# doanthue_13_4_2020.net
KiCad netlist of a schematic drawn in Altium Designer
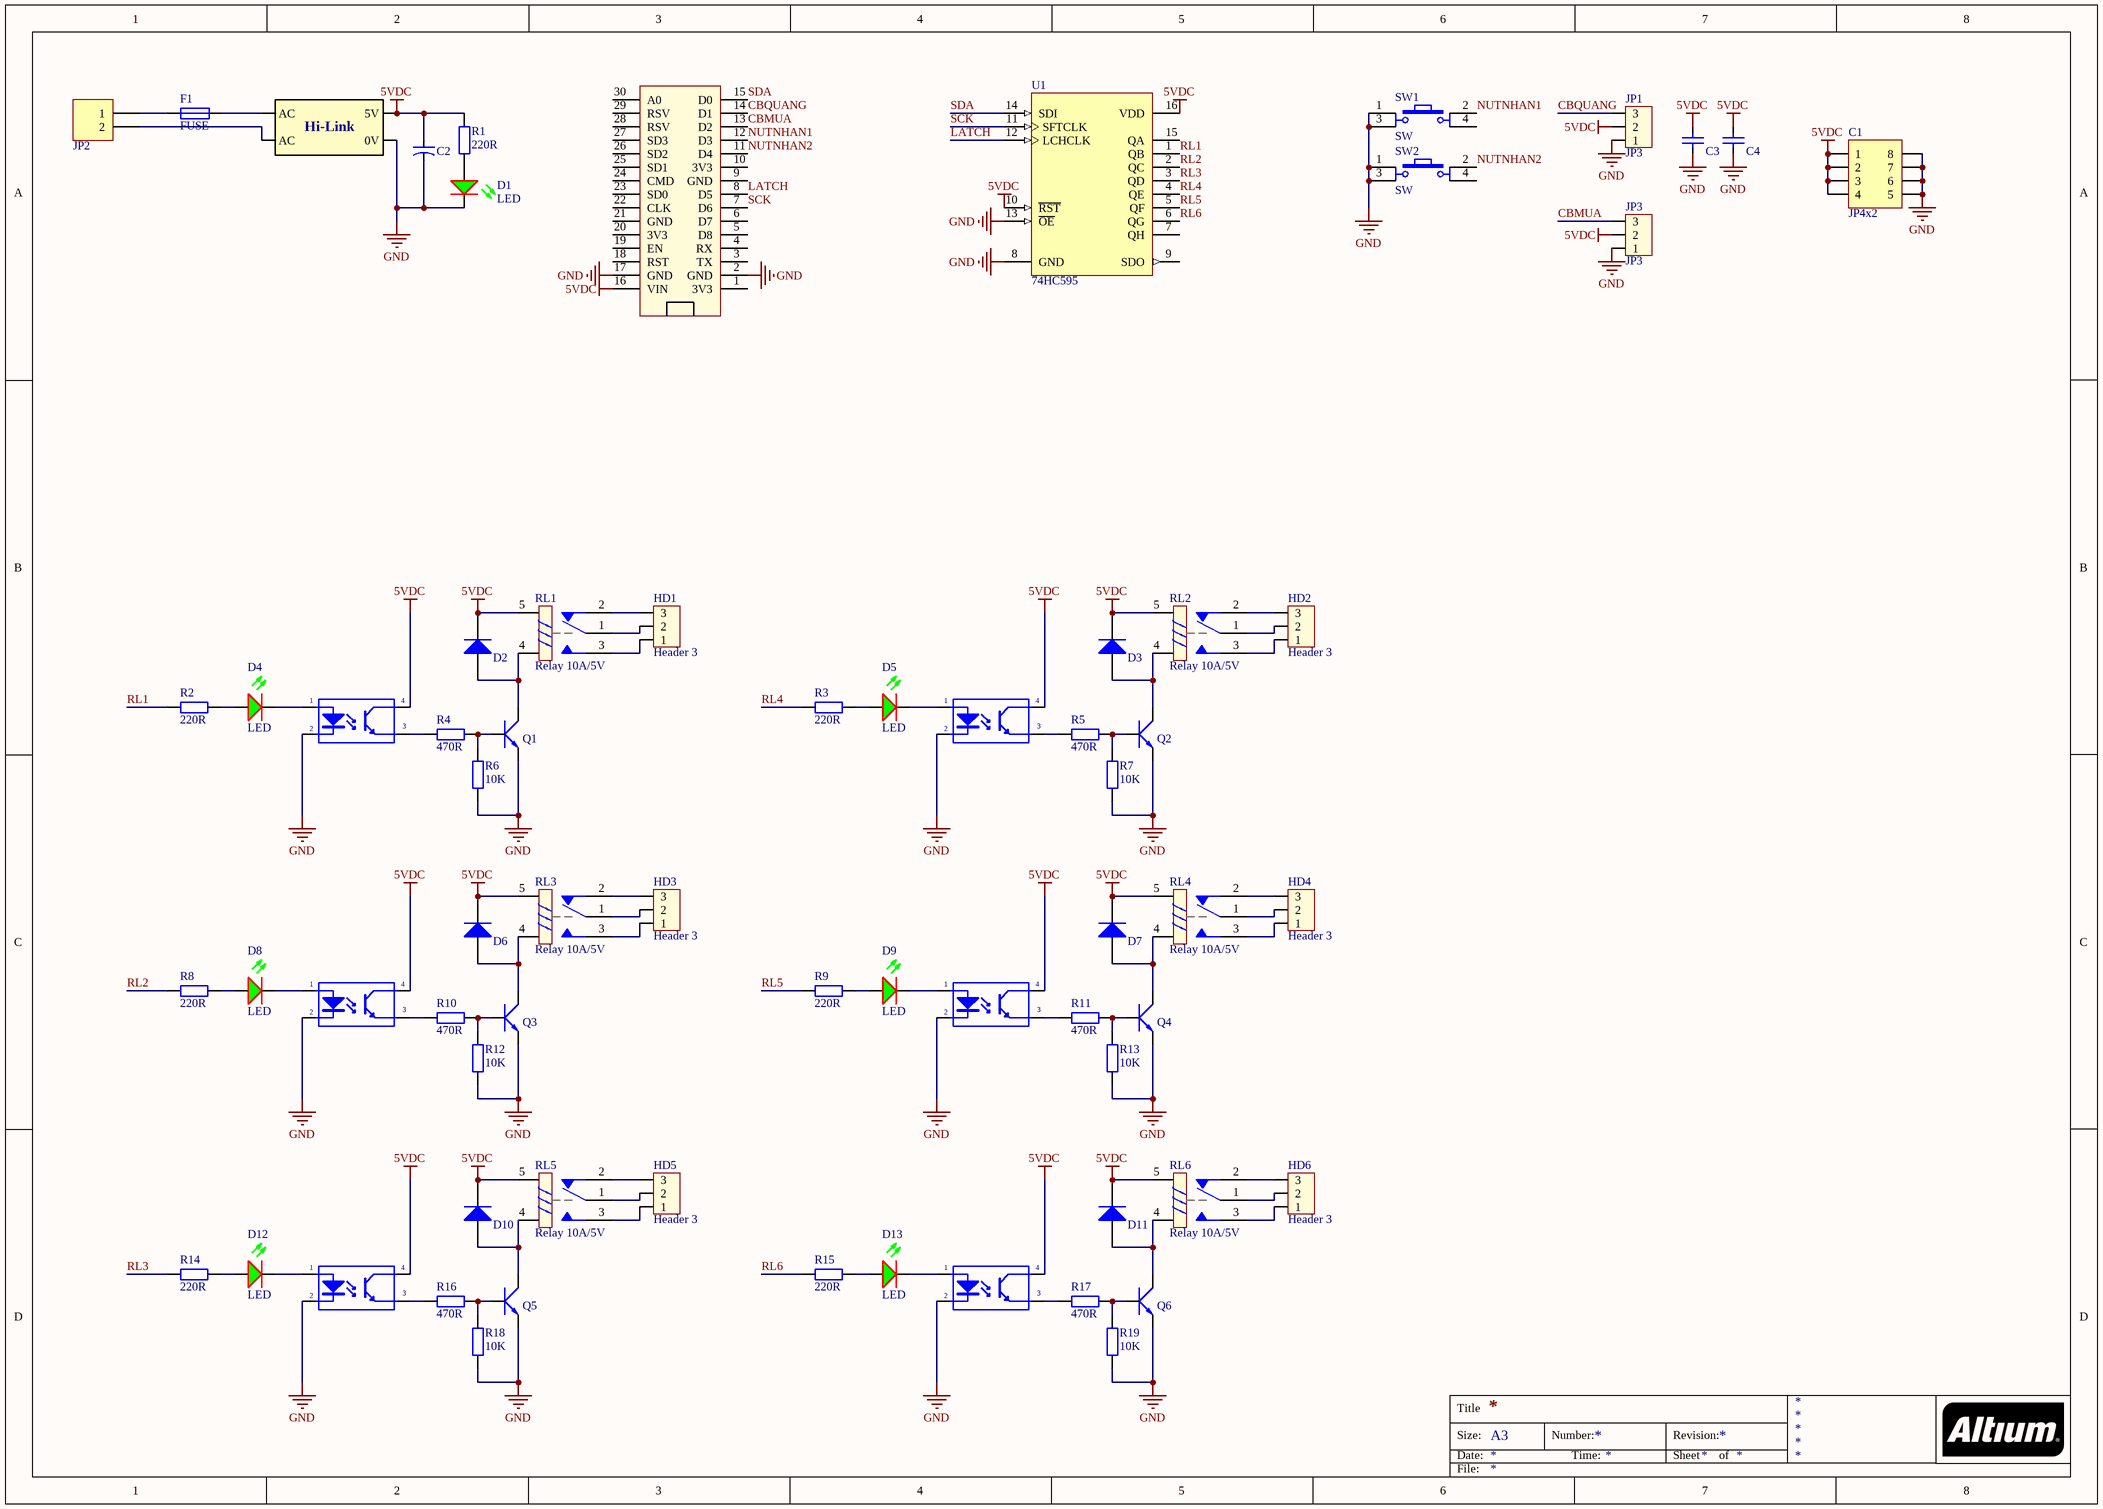
[diagram p0: doanthue_13_4_2020.SchDoc]

(export (version "E")
  (design (tool "Eeschema 10.0.6"))
  (components
    (comp (ref "*1")
      (value "Hi-Link")
      (footprint "Hi-Link")
      (libsource (lib "Lib_NTD_HaUI") (part "Hi-Link"))
    )
    (comp (ref "*2")
      (value "Module ESP8266 CP2102")
      (footprint "Module ESP8266 CP2102")
      (libsource (lib "Lib_NTD_HaUI") (part "Module ESP8266 CP2102"))
    )
    (comp (ref "C1")
      (value "JP4x2")
      (footprint "JP4-D2T")
      (description "WR-PHD 2.54 mm Dual Socket Header")
      (fields
        (field (name "MANUFACTURER") "Würth Elektronik eiSos GmbH")
        (field (name "PARTNO") "61300821821")
        (field (name "CREATED BY") "Karrer Zheng")
      )
      (libsource (lib "LIBRARY") (part "JP4x2"))
    )
    (comp (ref "C2")
      (value "10uF")
      (footprint "CA-ALU-2.54")
      (description "Capacitor (Semiconductor SIM Model)")
      (fields (field (name "PUBLISHER") "Altium Limited"))
      (libsource (lib "LIBRARY") (part "CN-ALU-DIP"))
    )
    (comp (ref "C3")
      (value "0805 104")
      (footprint "CAP-0805-SC")
      (libsource (lib "AltiumLibraryTieuBao") (part "CAP-SMDCHIP"))
    )
    (comp (ref "C4")
      (value "0805 104")
      (footprint "CAP-0805-SC")
      (libsource (lib "AltiumLibraryTieuBao") (part "CAP-SMDCHIP"))
    )
    (comp (ref "D1")
      (value "LED")
      (footprint "LED_SMD_0805")
      (libsource (lib "AltiumLibraryTieuBao") (part "LED"))
    )
    (comp (ref "D2") (value "DIODE") (footprint "DO 214AC") (libsource (lib "Lib_NTD_HaUI") (part "DIODE")))
    (comp (ref "D3") (value "DIODE") (footprint "DO 214AC") (libsource (lib "Lib_NTD_HaUI") (part "DIODE")))
    (comp (ref "D4")
      (value "LED")
      (footprint "LED_SMD_0805")
      (libsource (lib "AltiumLibraryTieuBao") (part "LED"))
    )
    (comp (ref "D5")
      (value "LED")
      (footprint "LED_SMD_0805")
      (libsource (lib "AltiumLibraryTieuBao") (part "LED"))
    )
    (comp (ref "D6") (value "DIODE") (footprint "DO 214AC") (libsource (lib "Lib_NTD_HaUI") (part "DIODE")))
    (comp (ref "D7") (value "DIODE") (footprint "DO 214AC") (libsource (lib "Lib_NTD_HaUI") (part "DIODE")))
    (comp (ref "D8")
      (value "LED")
      (footprint "LED_SMD_0805")
      (libsource (lib "AltiumLibraryTieuBao") (part "LED"))
    )
    (comp (ref "D9")
      (value "LED")
      (footprint "LED_SMD_0805")
      (libsource (lib "AltiumLibraryTieuBao") (part "LED"))
    )
    (comp (ref "D10") (value "DIODE") (footprint "DO 214AC") (libsource (lib "Lib_NTD_HaUI") (part "DIODE")))
    (comp (ref "D11") (value "DIODE") (footprint "DO 214AC") (libsource (lib "Lib_NTD_HaUI") (part "DIODE")))
    (comp (ref "D12")
      (value "LED")
      (footprint "LED_SMD_0805")
      (libsource (lib "AltiumLibraryTieuBao") (part "LED"))
    )
    (comp (ref "D13")
      (value "LED")
      (footprint "LED_SMD_0805")
      (libsource (lib "AltiumLibraryTieuBao") (part "LED"))
    )
    (comp (ref "F1")
      (value "FUSE")
      (footprint "FUSE-SC")
      (libsource (lib "AltiumLibraryTieuBao") (part "FUSE"))
    )
    (comp (ref "HD1")
      (value "Header 3")
      (footprint "HED3")
      (description "Header 3 (Green)")
      (libsource (lib "syhaunguyen") (part "Hed3"))
    )
    (comp (ref "HD2")
      (value "Header 3")
      (footprint "HED3")
      (description "Header 3 (Green)")
      (libsource (lib "syhaunguyen") (part "Hed3"))
    )
    (comp (ref "HD3")
      (value "Header 3")
      (footprint "HED3")
      (description "Header 3 (Green)")
      (libsource (lib "syhaunguyen") (part "Hed3"))
    )
    (comp (ref "HD4")
      (value "Header 3")
      (footprint "HED3")
      (description "Header 3 (Green)")
      (libsource (lib "syhaunguyen") (part "Hed3"))
    )
    (comp (ref "HD5")
      (value "Header 3")
      (footprint "HED3")
      (description "Header 3 (Green)")
      (libsource (lib "syhaunguyen") (part "Hed3"))
    )
    (comp (ref "HD6")
      (value "Header 3")
      (footprint "HED3")
      (description "Header 3 (Green)")
      (libsource (lib "syhaunguyen") (part "Hed3"))
    )
    (comp (ref "JP1")
      (value "JP3")
      (footprint "CON3")
      (description "Connector 3")
      (libsource (lib "syhaunguyen") (part "Con3"))
    )
    (comp (ref "JP2")
      (value "Header 2_1")
      (footprint "HED2")
      (description "Header, 2-Pin")
      (fields (field (name "MANUFACTURER") "Generic Components"))
      (libsource (lib "syhaunguyen") (part "Header 2_1"))
    )
    (comp (ref "JP3")
      (value "JP3")
      (footprint "CON3")
      (description "Connector 3")
      (libsource (lib "syhaunguyen") (part "Con3"))
    )
    (comp (ref "Q1") (value "C1815") (footprint "SOT23") (libsource (lib "Lib_NTD_HaUI") (part "C1815")))
    (comp (ref "Q2") (value "C1815") (footprint "SOT23") (libsource (lib "Lib_NTD_HaUI") (part "C1815")))
    (comp (ref "Q3") (value "C1815") (footprint "SOT23") (libsource (lib "Lib_NTD_HaUI") (part "C1815")))
    (comp (ref "Q4") (value "C1815") (footprint "SOT23") (libsource (lib "Lib_NTD_HaUI") (part "C1815")))
    (comp (ref "Q5") (value "C1815") (footprint "SOT23") (libsource (lib "Lib_NTD_HaUI") (part "C1815")))
    (comp (ref "Q6") (value "C1815") (footprint "SOT23") (libsource (lib "Lib_NTD_HaUI") (part "C1815")))
    (comp (ref "R1")
      (value "220R")
      (footprint "SM-RES-0805")
      (description "Resistor 1/4W")
      (libsource (lib "syhaunguyen") (part "R1/4W"))
    )
    (comp (ref "R2")
      (value "220R")
      (footprint "SM-RES-0805")
      (description "Resistor 1/4W")
      (libsource (lib "syhaunguyen") (part "R1/4W"))
    )
    (comp (ref "R3")
      (value "220R")
      (footprint "SM-RES-0805")
      (description "Resistor 1/4W")
      (libsource (lib "syhaunguyen") (part "R1/4W"))
    )
    (comp (ref "R4")
      (value "470R")
      (footprint "SM-RES-0805")
      (description "Resistor 1/4W")
      (libsource (lib "syhaunguyen") (part "R1/4W"))
    )
    (comp (ref "R5")
      (value "470R")
      (footprint "SM-RES-0805")
      (description "Resistor 1/4W")
      (libsource (lib "syhaunguyen") (part "R1/4W"))
    )
    (comp (ref "R6")
      (value "10K")
      (footprint "SM-RES-0805")
      (description "Resistor 1/4W")
      (libsource (lib "syhaunguyen") (part "R1/4W"))
    )
    (comp (ref "R7")
      (value "10K")
      (footprint "SM-RES-0805")
      (description "Resistor 1/4W")
      (libsource (lib "syhaunguyen") (part "R1/4W"))
    )
    (comp (ref "R8")
      (value "220R")
      (footprint "SM-RES-0805")
      (description "Resistor 1/4W")
      (libsource (lib "syhaunguyen") (part "R1/4W"))
    )
    (comp (ref "R9")
      (value "220R")
      (footprint "SM-RES-0805")
      (description "Resistor 1/4W")
      (libsource (lib "syhaunguyen") (part "R1/4W"))
    )
    (comp (ref "R10")
      (value "470R")
      (footprint "SM-RES-0805")
      (description "Resistor 1/4W")
      (libsource (lib "syhaunguyen") (part "R1/4W"))
    )
    (comp (ref "R11")
      (value "470R")
      (footprint "SM-RES-0805")
      (description "Resistor 1/4W")
      (libsource (lib "syhaunguyen") (part "R1/4W"))
    )
    (comp (ref "R12")
      (value "10K")
      (footprint "SM-RES-0805")
      (description "Resistor 1/4W")
      (libsource (lib "syhaunguyen") (part "R1/4W"))
    )
    (comp (ref "R13")
      (value "10K")
      (footprint "SM-RES-0805")
      (description "Resistor 1/4W")
      (libsource (lib "syhaunguyen") (part "R1/4W"))
    )
    (comp (ref "R14")
      (value "220R")
      (footprint "SM-RES-0805")
      (description "Resistor 1/4W")
      (libsource (lib "syhaunguyen") (part "R1/4W"))
    )
    (comp (ref "R15")
      (value "220R")
      (footprint "SM-RES-0805")
      (description "Resistor 1/4W")
      (libsource (lib "syhaunguyen") (part "R1/4W"))
    )
    (comp (ref "R16")
      (value "470R")
      (footprint "SM-RES-0805")
      (description "Resistor 1/4W")
      (libsource (lib "syhaunguyen") (part "R1/4W"))
    )
    (comp (ref "R17")
      (value "470R")
      (footprint "SM-RES-0805")
      (description "Resistor 1/4W")
      (libsource (lib "syhaunguyen") (part "R1/4W"))
    )
    (comp (ref "R18")
      (value "10K")
      (footprint "SM-RES-0805")
      (description "Resistor 1/4W")
      (libsource (lib "syhaunguyen") (part "R1/4W"))
    )
    (comp (ref "R19")
      (value "10K")
      (footprint "SM-RES-0805")
      (description "Resistor 1/4W")
      (libsource (lib "syhaunguyen") (part "R1/4W"))
    )
    (comp (ref "RL1")
      (value "Relay 10A/5V")
      (footprint "RL_SPDT_10A")
      (description "Relay SPDT,10A - 12VDC 5 Pin")
      (libsource (lib "syhaunguyen") (part "Relay 1"))
    )
    (comp (ref "RL2")
      (value "Relay 10A/5V")
      (footprint "RL_SPDT_10A")
      (description "Relay SPDT,10A - 12VDC 5 Pin")
      (libsource (lib "syhaunguyen") (part "Relay 1"))
    )
    (comp (ref "RL3")
      (value "Relay 10A/5V")
      (footprint "RL_SPDT_10A")
      (description "Relay SPDT,10A - 12VDC 5 Pin")
      (libsource (lib "syhaunguyen") (part "Relay 1"))
    )
    (comp (ref "RL4")
      (value "Relay 10A/5V")
      (footprint "RL_SPDT_10A")
      (description "Relay SPDT,10A - 12VDC 5 Pin")
      (libsource (lib "syhaunguyen") (part "Relay 1"))
    )
    (comp (ref "RL5")
      (value "Relay 10A/5V")
      (footprint "RL_SPDT_10A")
      (description "Relay SPDT,10A - 12VDC 5 Pin")
      (libsource (lib "syhaunguyen") (part "Relay 1"))
    )
    (comp (ref "RL6")
      (value "Relay 10A/5V")
      (footprint "RL_SPDT_10A")
      (description "Relay SPDT,10A - 12VDC 5 Pin")
      (libsource (lib "syhaunguyen") (part "Relay 1"))
    )
    (comp (ref "SW1")
      (value "SW")
      (footprint "SW4B")
      (description "Switch button 4 pin")
      (libsource (lib "syhaunguyen") (part "SW4"))
    )
    (comp (ref "SW2")
      (value "SW")
      (footprint "SW4B")
      (description "Switch button 4 pin")
      (libsource (lib "syhaunguyen") (part "SW4"))
    )
    (comp (ref "U1")
      (value "74HC595")
      (footprint "SO-16-M")
      (libsource (lib "AltiumLibraryTieuBao") (part "74HC595"))
    )
    (comp (ref "U2") (value "PC817") (footprint "PC817") (libsource (lib "Lib_NTD_HaUI") (part "PC817")))
    (comp (ref "U3") (value "PC817") (footprint "PC817") (libsource (lib "Lib_NTD_HaUI") (part "PC817")))
    (comp (ref "U4") (value "PC817") (footprint "PC817") (libsource (lib "Lib_NTD_HaUI") (part "PC817")))
    (comp (ref "U5") (value "PC817") (footprint "PC817") (libsource (lib "Lib_NTD_HaUI") (part "PC817")))
    (comp (ref "U6") (value "PC817") (footprint "PC817") (libsource (lib "Lib_NTD_HaUI") (part "PC817")))
    (comp (ref "U7") (value "PC817") (footprint "PC817") (libsource (lib "Lib_NTD_HaUI") (part "PC817")))
  )
  (nets
    (net (code "1") (name "/CBMUA") (class "Default")
      (node (ref "*2") (pin "13") (pinfunction "D2_13") (pintype "passive"))
      (node (ref "JP3") (pin "3") (pinfunction "3_3") (pintype "passive"))
    )
    (net (code "2") (name "/CBQUANG") (class "Default")
      (node (ref "*2") (pin "14") (pinfunction "D1_14") (pintype "passive"))
      (node (ref "JP1") (pin "3") (pinfunction "3_3") (pintype "passive"))
    )
    (net (code "3") (name "/LATCH") (class "Default")
      (node (ref "*2") (pin "8") (pinfunction "D5_8") (pintype "passive"))
      (node (ref "U1") (pin "12") (pinfunction "LCHCLK_12") (pintype "input"))
    )
    (net (code "4") (name "/NUTNHAN1") (class "Default")
      (node (ref "*2") (pin "12") (pinfunction "D3_12") (pintype "passive"))
      (node (ref "SW1") (pin "2") (pintype "passive"))
    )
    (net (code "5") (name "/NUTNHAN2") (class "Default")
      (node (ref "*2") (pin "11") (pinfunction "D4_11") (pintype "passive"))
      (node (ref "SW2") (pin "2") (pintype "passive"))
    )
    (net (code "6") (name "/RL1") (class "Default")
      (node (ref "R2") (pin "1") (pinfunction "1_1") (pintype "passive"))
      (node (ref "U1") (pin "1") (pinfunction "QB_1") (pintype "tri_state"))
    )
    (net (code "7") (name "/RL2") (class "Default")
      (node (ref "R8") (pin "1") (pinfunction "1_1") (pintype "passive"))
      (node (ref "U1") (pin "2") (pinfunction "QC_2") (pintype "tri_state"))
    )
    (net (code "8") (name "/RL3") (class "Default")
      (node (ref "R14") (pin "1") (pinfunction "1_1") (pintype "passive"))
      (node (ref "U1") (pin "3") (pinfunction "QD_3") (pintype "tri_state"))
    )
    (net (code "9") (name "/RL4") (class "Default")
      (node (ref "R3") (pin "1") (pinfunction "1_1") (pintype "passive"))
      (node (ref "U1") (pin "4") (pinfunction "QE_4") (pintype "tri_state"))
    )
    (net (code "10") (name "/RL5") (class "Default")
      (node (ref "R9") (pin "1") (pinfunction "1_1") (pintype "passive"))
      (node (ref "U1") (pin "5") (pinfunction "QF_5") (pintype "tri_state"))
    )
    (net (code "11") (name "/RL6") (class "Default")
      (node (ref "R15") (pin "1") (pinfunction "1_1") (pintype "passive"))
      (node (ref "U1") (pin "6") (pinfunction "QG_6") (pintype "tri_state"))
    )
    (net (code "12") (name "/SCK") (class "Default")
      (node (ref "*2") (pin "7") (pinfunction "D6_7") (pintype "passive"))
      (node (ref "U1") (pin "11") (pinfunction "SFTCLK_11") (pintype "input"))
    )
    (net (code "13") (name "/SDA") (class "Default")
      (node (ref "*2") (pin "15") (pinfunction "D0_15") (pintype "passive"))
      (node (ref "U1") (pin "14") (pinfunction "SDI_14") (pintype "input"))
    )
    (net (code "14") (name "5VDC") (class "Default")
      (node (ref "*1") (pin "4") (pinfunction "5V_4") (pintype "passive"))
      (node (ref "*2") (pin "16") (pinfunction "VIN_16") (pintype "passive"))
      (node (ref "C1") (pin "1") (pinfunction "1_1") (pintype "passive"))
      (node (ref "C1") (pin "2") (pinfunction "2_2") (pintype "passive"))
      (node (ref "C1") (pin "3") (pinfunction "3_3") (pintype "passive"))
      (node (ref "C1") (pin "4") (pinfunction "4_4") (pintype "passive"))
      (node (ref "C2") (pin "1") (pinfunction "1_1") (pintype "passive"))
      (node (ref "C3") (pin "1") (pinfunction "1_1") (pintype "passive"))
      (node (ref "C4") (pin "1") (pinfunction "1_1") (pintype "passive"))
      (node (ref "D10") (pin "2") (pinfunction "K_2") (pintype "passive"))
      (node (ref "D11") (pin "2") (pinfunction "K_2") (pintype "passive"))
      (node (ref "D2") (pin "2") (pinfunction "K_2") (pintype "passive"))
      (node (ref "D3") (pin "2") (pinfunction "K_2") (pintype "passive"))
      (node (ref "D6") (pin "2") (pinfunction "K_2") (pintype "passive"))
      (node (ref "D7") (pin "2") (pinfunction "K_2") (pintype "passive"))
      (node (ref "JP1") (pin "2") (pinfunction "2_2") (pintype "passive"))
      (node (ref "JP3") (pin "2") (pinfunction "2_2") (pintype "passive"))
      (node (ref "R1") (pin "2") (pinfunction "2_2") (pintype "passive"))
      (node (ref "RL1") (pin "5") (pinfunction "5_5") (pintype "passive"))
      (node (ref "RL2") (pin "5") (pinfunction "5_5") (pintype "passive"))
      (node (ref "RL3") (pin "5") (pinfunction "5_5") (pintype "passive"))
      (node (ref "RL4") (pin "5") (pinfunction "5_5") (pintype "passive"))
      (node (ref "RL5") (pin "5") (pinfunction "5_5") (pintype "passive"))
      (node (ref "RL6") (pin "5") (pinfunction "5_5") (pintype "passive"))
      (node (ref "U1") (pin "10") (pinfunction "~{RST}_10") (pintype "input"))
      (node (ref "U1") (pin "16") (pinfunction "VDD_16") (pintype "power_in"))
      (node (ref "U2") (pin "4") (pinfunction "C_4") (pintype "passive"))
      (node (ref "U3") (pin "4") (pinfunction "C_4") (pintype "passive"))
      (node (ref "U4") (pin "4") (pinfunction "C_4") (pintype "passive"))
      (node (ref "U5") (pin "4") (pinfunction "C_4") (pintype "passive"))
      (node (ref "U6") (pin "4") (pinfunction "C_4") (pintype "passive"))
      (node (ref "U7") (pin "4") (pinfunction "C_4") (pintype "passive"))
    )
    (net (code "15") (name "GND") (class "Default")
      (node (ref "*1") (pin "3") (pinfunction "0V_3") (pintype "passive"))
      (node (ref "*2") (pin "17") (pinfunction "GND_17") (pintype "passive"))
      (node (ref "*2") (pin "2") (pinfunction "GND_2") (pintype "passive"))
      (node (ref "C1") (pin "5") (pinfunction "5_5") (pintype "passive"))
      (node (ref "C1") (pin "6") (pinfunction "6_6") (pintype "passive"))
      (node (ref "C1") (pin "7") (pinfunction "7_7") (pintype "passive"))
      (node (ref "C1") (pin "8") (pinfunction "8_8") (pintype "passive"))
      (node (ref "C2") (pin "2") (pinfunction "2_2") (pintype "passive"))
      (node (ref "C3") (pin "2") (pinfunction "2_2") (pintype "passive"))
      (node (ref "C4") (pin "2") (pinfunction "2_2") (pintype "passive"))
      (node (ref "D1") (pin "2") (pinfunction "K_2") (pintype "passive"))
      (node (ref "JP1") (pin "1") (pinfunction "1_1") (pintype "passive"))
      (node (ref "JP3") (pin "1") (pinfunction "1_1") (pintype "passive"))
      (node (ref "Q1") (pin "2") (pinfunction "E_2") (pintype "passive"))
      (node (ref "Q2") (pin "2") (pinfunction "E_2") (pintype "passive"))
      (node (ref "Q3") (pin "2") (pinfunction "E_2") (pintype "passive"))
      (node (ref "Q4") (pin "2") (pinfunction "E_2") (pintype "passive"))
      (node (ref "Q5") (pin "2") (pinfunction "E_2") (pintype "passive"))
      (node (ref "Q6") (pin "2") (pinfunction "E_2") (pintype "passive"))
      (node (ref "R12") (pin "1") (pinfunction "1_1") (pintype "passive"))
      (node (ref "R13") (pin "1") (pinfunction "1_1") (pintype "passive"))
      (node (ref "R18") (pin "1") (pinfunction "1_1") (pintype "passive"))
      (node (ref "R19") (pin "1") (pinfunction "1_1") (pintype "passive"))
      (node (ref "R6") (pin "1") (pinfunction "1_1") (pintype "passive"))
      (node (ref "R7") (pin "1") (pinfunction "1_1") (pintype "passive"))
      (node (ref "SW1") (pin "1") (pintype "passive"))
      (node (ref "SW1") (pin "3") (pintype "passive"))
      (node (ref "SW2") (pin "1") (pintype "passive"))
      (node (ref "SW2") (pin "3") (pintype "passive"))
      (node (ref "U1") (pin "13") (pinfunction "~{OE}_13") (pintype "input"))
      (node (ref "U1") (pin "8") (pinfunction "GND_8") (pintype "power_in"))
      (node (ref "U2") (pin "2") (pinfunction "K_2") (pintype "passive"))
      (node (ref "U3") (pin "2") (pinfunction "K_2") (pintype "passive"))
      (node (ref "U4") (pin "2") (pinfunction "K_2") (pintype "passive"))
      (node (ref "U5") (pin "2") (pinfunction "K_2") (pintype "passive"))
      (node (ref "U6") (pin "2") (pinfunction "K_2") (pintype "passive"))
      (node (ref "U7") (pin "2") (pinfunction "K_2") (pintype "passive"))
    )
    (net (code "16") (name "Net-(*1-AC-Pad2)") (class "Default")
      (node (ref "*1") (pin "2") (pinfunction "AC_2") (pintype "passive"))
      (node (ref "JP2") (pin "2") (pinfunction "2_2") (pintype "passive"))
    )
    (net (code "17") (name "Net-(D1-A)") (class "Default")
      (node (ref "D1") (pin "1") (pinfunction "A_1") (pintype "passive"))
      (node (ref "R1") (pin "1") (pinfunction "1_1") (pintype "passive"))
    )
    (net (code "18") (name "Net-(D2-A)") (class "Default")
      (node (ref "D2") (pin "1") (pinfunction "A_1") (pintype "passive"))
      (node (ref "Q1") (pin "3") (pinfunction "C_3") (pintype "passive"))
      (node (ref "RL1") (pin "4") (pinfunction "4_4") (pintype "passive"))
    )
    (net (code "19") (name "Net-(D3-A)") (class "Default")
      (node (ref "D3") (pin "1") (pinfunction "A_1") (pintype "passive"))
      (node (ref "Q2") (pin "3") (pinfunction "C_3") (pintype "passive"))
      (node (ref "RL2") (pin "4") (pinfunction "4_4") (pintype "passive"))
    )
    (net (code "20") (name "Net-(D4-A)") (class "Default")
      (node (ref "D4") (pin "1") (pinfunction "A_1") (pintype "passive"))
      (node (ref "R2") (pin "2") (pinfunction "2_2") (pintype "passive"))
    )
    (net (code "21") (name "Net-(D4-K)") (class "Default")
      (node (ref "D4") (pin "2") (pinfunction "K_2") (pintype "passive"))
      (node (ref "U2") (pin "1") (pinfunction "A_1") (pintype "passive"))
    )
    (net (code "22") (name "Net-(D5-A)") (class "Default")
      (node (ref "D5") (pin "1") (pinfunction "A_1") (pintype "passive"))
      (node (ref "R3") (pin "2") (pinfunction "2_2") (pintype "passive"))
    )
    (net (code "23") (name "Net-(D5-K)") (class "Default")
      (node (ref "D5") (pin "2") (pinfunction "K_2") (pintype "passive"))
      (node (ref "U3") (pin "1") (pinfunction "A_1") (pintype "passive"))
    )
    (net (code "24") (name "Net-(D6-A)") (class "Default")
      (node (ref "D6") (pin "1") (pinfunction "A_1") (pintype "passive"))
      (node (ref "Q3") (pin "3") (pinfunction "C_3") (pintype "passive"))
      (node (ref "RL3") (pin "4") (pinfunction "4_4") (pintype "passive"))
    )
    (net (code "25") (name "Net-(D7-A)") (class "Default")
      (node (ref "D7") (pin "1") (pinfunction "A_1") (pintype "passive"))
      (node (ref "Q4") (pin "3") (pinfunction "C_3") (pintype "passive"))
      (node (ref "RL4") (pin "4") (pinfunction "4_4") (pintype "passive"))
    )
    (net (code "26") (name "Net-(D8-A)") (class "Default")
      (node (ref "D8") (pin "1") (pinfunction "A_1") (pintype "passive"))
      (node (ref "R8") (pin "2") (pinfunction "2_2") (pintype "passive"))
    )
    (net (code "27") (name "Net-(D8-K)") (class "Default")
      (node (ref "D8") (pin "2") (pinfunction "K_2") (pintype "passive"))
      (node (ref "U4") (pin "1") (pinfunction "A_1") (pintype "passive"))
    )
    (net (code "28") (name "Net-(D9-A)") (class "Default")
      (node (ref "D9") (pin "1") (pinfunction "A_1") (pintype "passive"))
      (node (ref "R9") (pin "2") (pinfunction "2_2") (pintype "passive"))
    )
    (net (code "29") (name "Net-(D9-K)") (class "Default")
      (node (ref "D9") (pin "2") (pinfunction "K_2") (pintype "passive"))
      (node (ref "U5") (pin "1") (pinfunction "A_1") (pintype "passive"))
    )
    (net (code "30") (name "Net-(D10-A)") (class "Default")
      (node (ref "D10") (pin "1") (pinfunction "A_1") (pintype "passive"))
      (node (ref "Q5") (pin "3") (pinfunction "C_3") (pintype "passive"))
      (node (ref "RL5") (pin "4") (pinfunction "4_4") (pintype "passive"))
    )
    (net (code "31") (name "Net-(D11-A)") (class "Default")
      (node (ref "D11") (pin "1") (pinfunction "A_1") (pintype "passive"))
      (node (ref "Q6") (pin "3") (pinfunction "C_3") (pintype "passive"))
      (node (ref "RL6") (pin "4") (pinfunction "4_4") (pintype "passive"))
    )
    (net (code "32") (name "Net-(D12-A)") (class "Default")
      (node (ref "D12") (pin "1") (pinfunction "A_1") (pintype "passive"))
      (node (ref "R14") (pin "2") (pinfunction "2_2") (pintype "passive"))
    )
    (net (code "33") (name "Net-(D12-K)") (class "Default")
      (node (ref "D12") (pin "2") (pinfunction "K_2") (pintype "passive"))
      (node (ref "U6") (pin "1") (pinfunction "A_1") (pintype "passive"))
    )
    (net (code "34") (name "Net-(D13-A)") (class "Default")
      (node (ref "D13") (pin "1") (pinfunction "A_1") (pintype "passive"))
      (node (ref "R15") (pin "2") (pinfunction "2_2") (pintype "passive"))
    )
    (net (code "35") (name "Net-(D13-K)") (class "Default")
      (node (ref "D13") (pin "2") (pinfunction "K_2") (pintype "passive"))
      (node (ref "U7") (pin "1") (pinfunction "A_1") (pintype "passive"))
    )
    (net (code "36") (name "Net-(F1-100)") (class "Default")
      (node (ref "*1") (pin "1") (pinfunction "AC_1") (pintype "passive"))
      (node (ref "F1") (pin "2") (pinfunction "100_2") (pintype "passive"))
    )
    (net (code "37") (name "Net-(F1-Pad1)") (class "Default")
      (node (ref "F1") (pin "1") (pinfunction "1_1") (pintype "passive"))
      (node (ref "JP2") (pin "1") (pinfunction "1_1") (pintype "passive"))
    )
    (net (code "38") (name "Net-(HD1-Pad1)") (class "Default")
      (node (ref "HD1") (pin "1") (pinfunction "1_1") (pintype "passive"))
      (node (ref "RL1") (pin "3") (pinfunction "3_3") (pintype "passive"))
    )
    (net (code "39") (name "Net-(HD1-Pad2)") (class "Default")
      (node (ref "HD1") (pin "2") (pinfunction "2_2") (pintype "passive"))
      (node (ref "RL1") (pin "1") (pinfunction "1_1") (pintype "passive"))
    )
    (net (code "40") (name "Net-(HD1-Pad3)") (class "Default")
      (node (ref "HD1") (pin "3") (pinfunction "3_3") (pintype "passive"))
      (node (ref "RL1") (pin "2") (pinfunction "2_2") (pintype "passive"))
    )
    (net (code "41") (name "Net-(HD2-Pad1)") (class "Default")
      (node (ref "HD2") (pin "1") (pinfunction "1_1") (pintype "passive"))
      (node (ref "RL2") (pin "3") (pinfunction "3_3") (pintype "passive"))
    )
    (net (code "42") (name "Net-(HD2-Pad2)") (class "Default")
      (node (ref "HD2") (pin "2") (pinfunction "2_2") (pintype "passive"))
      (node (ref "RL2") (pin "1") (pinfunction "1_1") (pintype "passive"))
    )
    (net (code "43") (name "Net-(HD2-Pad3)") (class "Default")
      (node (ref "HD2") (pin "3") (pinfunction "3_3") (pintype "passive"))
      (node (ref "RL2") (pin "2") (pinfunction "2_2") (pintype "passive"))
    )
    (net (code "44") (name "Net-(HD3-Pad1)") (class "Default")
      (node (ref "HD3") (pin "1") (pinfunction "1_1") (pintype "passive"))
      (node (ref "RL3") (pin "3") (pinfunction "3_3") (pintype "passive"))
    )
    (net (code "45") (name "Net-(HD3-Pad2)") (class "Default")
      (node (ref "HD3") (pin "2") (pinfunction "2_2") (pintype "passive"))
      (node (ref "RL3") (pin "1") (pinfunction "1_1") (pintype "passive"))
    )
    (net (code "46") (name "Net-(HD3-Pad3)") (class "Default")
      (node (ref "HD3") (pin "3") (pinfunction "3_3") (pintype "passive"))
      (node (ref "RL3") (pin "2") (pinfunction "2_2") (pintype "passive"))
    )
    (net (code "47") (name "Net-(HD4-Pad1)") (class "Default")
      (node (ref "HD4") (pin "1") (pinfunction "1_1") (pintype "passive"))
      (node (ref "RL4") (pin "3") (pinfunction "3_3") (pintype "passive"))
    )
    (net (code "48") (name "Net-(HD4-Pad2)") (class "Default")
      (node (ref "HD4") (pin "2") (pinfunction "2_2") (pintype "passive"))
      (node (ref "RL4") (pin "1") (pinfunction "1_1") (pintype "passive"))
    )
    (net (code "49") (name "Net-(HD4-Pad3)") (class "Default")
      (node (ref "HD4") (pin "3") (pinfunction "3_3") (pintype "passive"))
      (node (ref "RL4") (pin "2") (pinfunction "2_2") (pintype "passive"))
    )
    (net (code "50") (name "Net-(HD5-Pad1)") (class "Default")
      (node (ref "HD5") (pin "1") (pinfunction "1_1") (pintype "passive"))
      (node (ref "RL5") (pin "3") (pinfunction "3_3") (pintype "passive"))
    )
    (net (code "51") (name "Net-(HD5-Pad2)") (class "Default")
      (node (ref "HD5") (pin "2") (pinfunction "2_2") (pintype "passive"))
      (node (ref "RL5") (pin "1") (pinfunction "1_1") (pintype "passive"))
    )
    (net (code "52") (name "Net-(HD5-Pad3)") (class "Default")
      (node (ref "HD5") (pin "3") (pinfunction "3_3") (pintype "passive"))
      (node (ref "RL5") (pin "2") (pinfunction "2_2") (pintype "passive"))
    )
    (net (code "53") (name "Net-(HD6-Pad1)") (class "Default")
      (node (ref "HD6") (pin "1") (pinfunction "1_1") (pintype "passive"))
      (node (ref "RL6") (pin "3") (pinfunction "3_3") (pintype "passive"))
    )
    (net (code "54") (name "Net-(HD6-Pad2)") (class "Default")
      (node (ref "HD6") (pin "2") (pinfunction "2_2") (pintype "passive"))
      (node (ref "RL6") (pin "1") (pinfunction "1_1") (pintype "passive"))
    )
    (net (code "55") (name "Net-(HD6-Pad3)") (class "Default")
      (node (ref "HD6") (pin "3") (pinfunction "3_3") (pintype "passive"))
      (node (ref "RL6") (pin "2") (pinfunction "2_2") (pintype "passive"))
    )
    (net (code "56") (name "Net-(Q1-B)") (class "Default")
      (node (ref "Q1") (pin "1") (pinfunction "B_1") (pintype "passive"))
      (node (ref "R4") (pin "2") (pinfunction "2_2") (pintype "passive"))
      (node (ref "R6") (pin "2") (pinfunction "2_2") (pintype "passive"))
    )
    (net (code "57") (name "Net-(Q2-B)") (class "Default")
      (node (ref "Q2") (pin "1") (pinfunction "B_1") (pintype "passive"))
      (node (ref "R5") (pin "2") (pinfunction "2_2") (pintype "passive"))
      (node (ref "R7") (pin "2") (pinfunction "2_2") (pintype "passive"))
    )
    (net (code "58") (name "Net-(Q3-B)") (class "Default")
      (node (ref "Q3") (pin "1") (pinfunction "B_1") (pintype "passive"))
      (node (ref "R10") (pin "2") (pinfunction "2_2") (pintype "passive"))
      (node (ref "R12") (pin "2") (pinfunction "2_2") (pintype "passive"))
    )
    (net (code "59") (name "Net-(Q4-B)") (class "Default")
      (node (ref "Q4") (pin "1") (pinfunction "B_1") (pintype "passive"))
      (node (ref "R11") (pin "2") (pinfunction "2_2") (pintype "passive"))
      (node (ref "R13") (pin "2") (pinfunction "2_2") (pintype "passive"))
    )
    (net (code "60") (name "Net-(Q5-B)") (class "Default")
      (node (ref "Q5") (pin "1") (pinfunction "B_1") (pintype "passive"))
      (node (ref "R16") (pin "2") (pinfunction "2_2") (pintype "passive"))
      (node (ref "R18") (pin "2") (pinfunction "2_2") (pintype "passive"))
    )
    (net (code "61") (name "Net-(Q6-B)") (class "Default")
      (node (ref "Q6") (pin "1") (pinfunction "B_1") (pintype "passive"))
      (node (ref "R17") (pin "2") (pinfunction "2_2") (pintype "passive"))
      (node (ref "R19") (pin "2") (pinfunction "2_2") (pintype "passive"))
    )
    (net (code "62") (name "Net-(U2-E)") (class "Default")
      (node (ref "R4") (pin "1") (pinfunction "1_1") (pintype "passive"))
      (node (ref "U2") (pin "3") (pinfunction "E_3") (pintype "passive"))
    )
    (net (code "63") (name "Net-(U3-E)") (class "Default")
      (node (ref "R5") (pin "1") (pinfunction "1_1") (pintype "passive"))
      (node (ref "U3") (pin "3") (pinfunction "E_3") (pintype "passive"))
    )
    (net (code "64") (name "Net-(U4-E)") (class "Default")
      (node (ref "R10") (pin "1") (pinfunction "1_1") (pintype "passive"))
      (node (ref "U4") (pin "3") (pinfunction "E_3") (pintype "passive"))
    )
    (net (code "65") (name "Net-(U5-E)") (class "Default")
      (node (ref "R11") (pin "1") (pinfunction "1_1") (pintype "passive"))
      (node (ref "U5") (pin "3") (pinfunction "E_3") (pintype "passive"))
    )
    (net (code "66") (name "Net-(U6-E)") (class "Default")
      (node (ref "R16") (pin "1") (pinfunction "1_1") (pintype "passive"))
      (node (ref "U6") (pin "3") (pinfunction "E_3") (pintype "passive"))
    )
    (net (code "67") (name "Net-(U7-E)") (class "Default")
      (node (ref "R17") (pin "1") (pinfunction "1_1") (pintype "passive"))
      (node (ref "U7") (pin "3") (pinfunction "E_3") (pintype "passive"))
    )
    (net (code "68") (name "unconnected-(*2-3V3-Pad1)") (class "Default")
      (node (ref "*2") (pin "1") (pinfunction "3V3_1") (pintype "passive"))
    )
    (net (code "69") (name "unconnected-(*2-3V3-Pad10)") (class "Default")
      (node (ref "*2") (pin "10") (pinfunction "3V3_10") (pintype "passive"))
    )
    (net (code "70") (name "unconnected-(*2-3V3-Pad20)") (class "Default")
      (node (ref "*2") (pin "20") (pinfunction "3V3_20") (pintype "passive"))
    )
    (net (code "71") (name "unconnected-(*2-A0-Pad30)") (class "Default")
      (node (ref "*2") (pin "30") (pinfunction "A0_30") (pintype "passive"))
    )
    (net (code "72") (name "unconnected-(*2-CLK-Pad22)") (class "Default")
      (node (ref "*2") (pin "22") (pinfunction "CLK_22") (pintype "passive"))
    )
    (net (code "73") (name "unconnected-(*2-CMD-Pad24)") (class "Default")
      (node (ref "*2") (pin "24") (pinfunction "CMD_24") (pintype "passive"))
    )
    (net (code "74") (name "unconnected-(*2-D7-Pad6)") (class "Default")
      (node (ref "*2") (pin "6") (pinfunction "D7_6") (pintype "passive"))
    )
    (net (code "75") (name "unconnected-(*2-D8-Pad5)") (class "Default")
      (node (ref "*2") (pin "5") (pinfunction "D8_5") (pintype "passive"))
    )
    (net (code "76") (name "unconnected-(*2-EN-Pad19)") (class "Default")
      (node (ref "*2") (pin "19") (pinfunction "EN_19") (pintype "passive"))
    )
    (net (code "77") (name "unconnected-(*2-GND-Pad9)") (class "Default")
      (node (ref "*2") (pin "9") (pinfunction "GND_9") (pintype "passive"))
    )
    (net (code "78") (name "unconnected-(*2-GND-Pad21)") (class "Default")
      (node (ref "*2") (pin "21") (pinfunction "GND_21") (pintype "passive"))
    )
    (net (code "79") (name "unconnected-(*2-RST-Pad18)") (class "Default")
      (node (ref "*2") (pin "18") (pinfunction "RST_18") (pintype "passive"))
    )
    (net (code "80") (name "unconnected-(*2-RSV-Pad28)") (class "Default")
      (node (ref "*2") (pin "28") (pinfunction "RSV_28") (pintype "passive"))
    )
    (net (code "81") (name "unconnected-(*2-RSV-Pad29)") (class "Default")
      (node (ref "*2") (pin "29") (pinfunction "RSV_29") (pintype "passive"))
    )
    (net (code "82") (name "unconnected-(*2-RX-Pad4)") (class "Default")
      (node (ref "*2") (pin "4") (pinfunction "RX_4") (pintype "passive"))
    )
    (net (code "83") (name "unconnected-(*2-SD0-Pad23)") (class "Default")
      (node (ref "*2") (pin "23") (pinfunction "SD0_23") (pintype "passive"))
    )
    (net (code "84") (name "unconnected-(*2-SD1-Pad25)") (class "Default")
      (node (ref "*2") (pin "25") (pinfunction "SD1_25") (pintype "passive"))
    )
    (net (code "85") (name "unconnected-(*2-SD2-Pad26)") (class "Default")
      (node (ref "*2") (pin "26") (pinfunction "SD2_26") (pintype "passive"))
    )
    (net (code "86") (name "unconnected-(*2-SD3-Pad27)") (class "Default")
      (node (ref "*2") (pin "27") (pinfunction "SD3_27") (pintype "passive"))
    )
    (net (code "87") (name "unconnected-(*2-TX-Pad3)") (class "Default")
      (node (ref "*2") (pin "3") (pinfunction "TX_3") (pintype "passive"))
    )
    (net (code "88") (name "unconnected-(SW1-Pad4)") (class "Default")
      (node (ref "SW1") (pin "4") (pintype "passive"))
    )
    (net (code "89") (name "unconnected-(SW2-Pad4)") (class "Default")
      (node (ref "SW2") (pin "4") (pintype "passive"))
    )
    (net (code "90") (name "unconnected-(U1-QA-Pad15)") (class "Default")
      (node (ref "U1") (pin "15") (pinfunction "QA_15") (pintype "tri_state"))
    )
    (net (code "91") (name "unconnected-(U1-QH-Pad7)") (class "Default")
      (node (ref "U1") (pin "7") (pinfunction "QH_7") (pintype "tri_state"))
    )
    (net (code "92") (name "unconnected-(U1-SDO-Pad9)") (class "Default")
      (node (ref "U1") (pin "9") (pinfunction "SDO_9") (pintype "output"))
    )
  )
)
